# PIC32MZ.net
KiCad netlist of a schematic drawn in Altium Designer
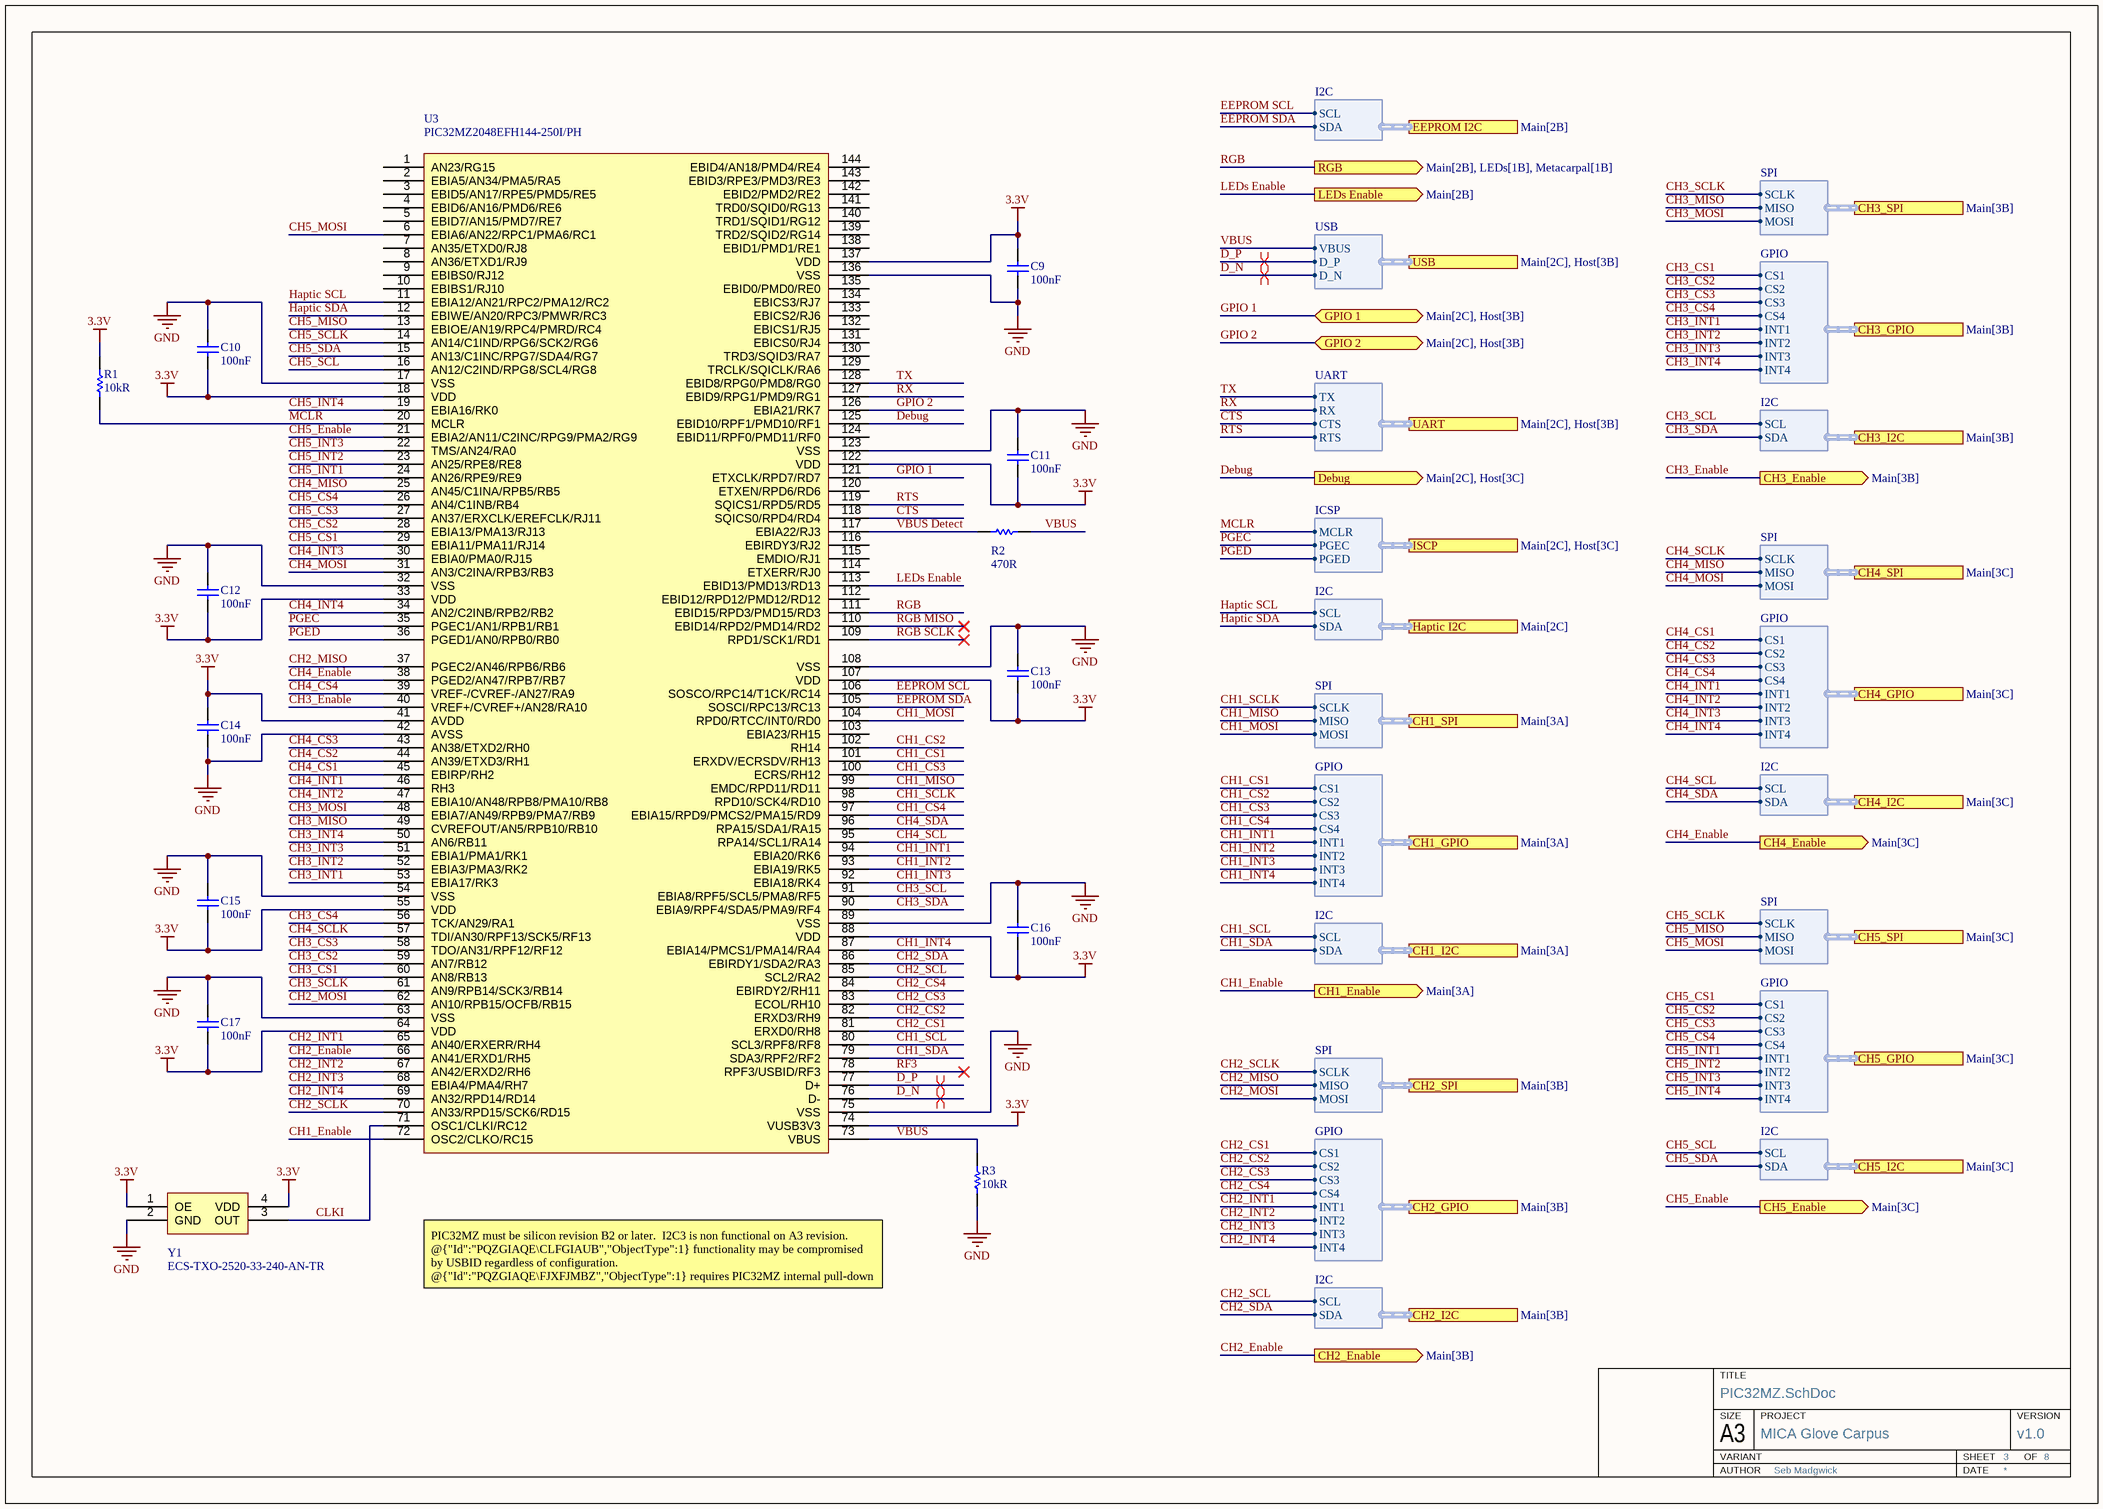
[diagram p0: PIC32MZ.SchDoc]

(export (version "E")
  (design (tool "Eeschema 10.0.6"))
  (components
    (comp (ref "C9") (value "100nF") (footprint "Capacitor 0402") (libsource (lib "x-io") (part "Capacitor")))
    (comp (ref "C10")
      (value "100nF")
      (footprint "Capacitor 0402")
      (libsource (lib "x-io") (part "Capacitor"))
    )
    (comp (ref "C11")
      (value "100nF")
      (footprint "Capacitor 0402")
      (libsource (lib "x-io") (part "Capacitor"))
    )
    (comp (ref "C12")
      (value "100nF")
      (footprint "Capacitor 0402")
      (libsource (lib "x-io") (part "Capacitor"))
    )
    (comp (ref "C13")
      (value "100nF")
      (footprint "Capacitor 0402")
      (libsource (lib "x-io") (part "Capacitor"))
    )
    (comp (ref "C14")
      (value "100nF")
      (footprint "Capacitor 0402")
      (libsource (lib "x-io") (part "Capacitor"))
    )
    (comp (ref "C15")
      (value "100nF")
      (footprint "Capacitor 0402")
      (libsource (lib "x-io") (part "Capacitor"))
    )
    (comp (ref "C16")
      (value "100nF")
      (footprint "Capacitor 0402")
      (libsource (lib "x-io") (part "Capacitor"))
    )
    (comp (ref "C17")
      (value "100nF")
      (footprint "Capacitor 0402")
      (libsource (lib "x-io") (part "Capacitor"))
    )
    (comp (ref "R1") (value "10kR") (footprint "Resistor 0402") (libsource (lib "x-io") (part "Resistor")))
    (comp (ref "R2") (value "470R") (footprint "Resistor 0402") (libsource (lib "x-io") (part "Resistor")))
    (comp (ref "R3") (value "10kR") (footprint "Resistor 0402") (libsource (lib "x-io") (part "Resistor")))
    (comp (ref "U3")
      (value "PIC32MZ2048EFH144-250I/PH")
      (footprint "TQFP-144 0.4mm")
      (libsource (lib "x-io") (part "PIC32MZ2048EFH144-250I/PH"))
    )
    (comp (ref "Y1")
      (value "ECS-TXO-2520-33-240-AN-TR")
      (footprint "ECS 2x2.5mm")
      (libsource (lib "x-io") (part "Oscillator"))
    )
  )
  (nets
    (net (code "7") (name "/CH1_CS1") (class "Default")
      (node (ref "U3") (pin "101") (pinfunction "ERXDV/ECRSDV/RH13_101") (pintype "passive"))
    )
    (net (code "8") (name "/CH1_CS2") (class "Default")
      (node (ref "U3") (pin "102") (pinfunction "RH14_102") (pintype "passive"))
    )
    (net (code "9") (name "/CH1_CS3") (class "Default")
      (node (ref "U3") (pin "100") (pinfunction "ECRS/RH12_100") (pintype "passive"))
    )
    (net (code "10") (name "/CH1_CS4") (class "Default")
      (node (ref "U3") (pin "97") (pinfunction "EBIA15/RPD9/PMCS2/PMA15/RD9_97") (pintype "passive"))
    )
    (net (code "11") (name "/CH1_Enable") (class "Default")
      (node (ref "U3") (pin "72") (pinfunction "OSC2/CLKO/RC15_72") (pintype "passive"))
    )
    (net (code "12") (name "/CH1_INT1") (class "Default")
      (node (ref "U3") (pin "94") (pinfunction "EBIA20/RK6_94") (pintype "passive"))
    )
    (net (code "13") (name "/CH1_INT2") (class "Default")
      (node (ref "U3") (pin "93") (pinfunction "EBIA19/RK5_93") (pintype "passive"))
    )
    (net (code "14") (name "/CH1_INT3") (class "Default")
      (node (ref "U3") (pin "92") (pinfunction "EBIA18/RK4_92") (pintype "passive"))
    )
    (net (code "15") (name "/CH1_INT4") (class "Default")
      (node (ref "U3") (pin "87") (pinfunction "EBIA14/PMCS1/PMA14/RA4_87") (pintype "passive"))
    )
    (net (code "16") (name "/CH1_MISO") (class "Default")
      (node (ref "U3") (pin "99") (pinfunction "EMDC/RPD11/RD11_99") (pintype "passive"))
    )
    (net (code "17") (name "/CH1_MOSI") (class "Default")
      (node (ref "U3") (pin "104") (pinfunction "RPD0/RTCC/INT0/RD0_104") (pintype "passive"))
    )
    (net (code "18") (name "/CH1_SCL") (class "Default")
      (node (ref "U3") (pin "80") (pinfunction "SCL3/RPF8/RF8_80") (pintype "passive"))
    )
    (net (code "19") (name "/CH1_SCLK") (class "Default")
      (node (ref "U3") (pin "98") (pinfunction "RPD10/SCK4/RD10_98") (pintype "passive"))
    )
    (net (code "20") (name "/CH1_SDA") (class "Default")
      (node (ref "U3") (pin "79") (pinfunction "SDA3/RPF2/RF2_79") (pintype "passive"))
    )
    (net (code "21") (name "/CH2_CS1") (class "Default")
      (node (ref "U3") (pin "81") (pinfunction "ERXD0/RH8_81") (pintype "passive"))
    )
    (net (code "22") (name "/CH2_CS2") (class "Default")
      (node (ref "U3") (pin "82") (pinfunction "ERXD3/RH9_82") (pintype "passive"))
    )
    (net (code "23") (name "/CH2_CS3") (class "Default")
      (node (ref "U3") (pin "83") (pinfunction "ECOL/RH10_83") (pintype "passive"))
    )
    (net (code "24") (name "/CH2_CS4") (class "Default")
      (node (ref "U3") (pin "84") (pinfunction "EBIRDY2/RH11_84") (pintype "passive"))
    )
    (net (code "25") (name "/CH2_Enable") (class "Default")
      (node (ref "U3") (pin "66") (pinfunction "AN41/ERXD1/RH5_66") (pintype "passive"))
    )
    (net (code "26") (name "/CH2_INT1") (class "Default")
      (node (ref "U3") (pin "65") (pinfunction "AN40/ERXERR/RH4_65") (pintype "passive"))
    )
    (net (code "27") (name "/CH2_INT2") (class "Default")
      (node (ref "U3") (pin "67") (pinfunction "AN42/ERXD2/RH6_67") (pintype "passive"))
    )
    (net (code "28") (name "/CH2_INT3") (class "Default")
      (node (ref "U3") (pin "68") (pinfunction "EBIA4/PMA4/RH7_68") (pintype "passive"))
    )
    (net (code "29") (name "/CH2_INT4") (class "Default")
      (node (ref "U3") (pin "69") (pinfunction "AN32/RPD14/RD14_69") (pintype "passive"))
    )
    (net (code "30") (name "/CH2_MISO") (class "Default")
      (node (ref "U3") (pin "37") (pinfunction "PGEC2/AN46/RPB6/RB6_37") (pintype "passive"))
    )
    (net (code "31") (name "/CH2_MOSI") (class "Default")
      (node (ref "U3") (pin "62") (pinfunction "AN10/RPB15/OCFB/RB15_62") (pintype "passive"))
    )
    (net (code "32") (name "/CH2_SCL") (class "Default")
      (node (ref "U3") (pin "85") (pinfunction "SCL2/RA2_85") (pintype "passive"))
    )
    (net (code "33") (name "/CH2_SCLK") (class "Default")
      (node (ref "U3") (pin "70") (pinfunction "AN33/RPD15/SCK6/RD15_70") (pintype "passive"))
    )
    (net (code "34") (name "/CH2_SDA") (class "Default")
      (node (ref "U3") (pin "86") (pinfunction "EBIRDY1/SDA2/RA3_86") (pintype "passive"))
    )
    (net (code "35") (name "/CH3_CS1") (class "Default")
      (node (ref "U3") (pin "60") (pinfunction "AN8/RB13_60") (pintype "passive"))
    )
    (net (code "36") (name "/CH3_CS2") (class "Default")
      (node (ref "U3") (pin "59") (pinfunction "AN7/RB12_59") (pintype "passive"))
    )
    (net (code "37") (name "/CH3_CS3") (class "Default")
      (node (ref "U3") (pin "58") (pinfunction "TDO/AN31/RPF12/RF12_58") (pintype "passive"))
    )
    (net (code "38") (name "/CH3_CS4") (class "Default")
      (node (ref "U3") (pin "56") (pinfunction "TCK/AN29/RA1_56") (pintype "passive"))
    )
    (net (code "39") (name "/CH3_Enable") (class "Default")
      (node (ref "U3") (pin "40") (pinfunction "VREF+/CVREF+/AN28/RA10_40") (pintype "passive"))
    )
    (net (code "40") (name "/CH3_INT1") (class "Default")
      (node (ref "U3") (pin "53") (pinfunction "EBIA17/RK3_53") (pintype "passive"))
    )
    (net (code "41") (name "/CH3_INT2") (class "Default")
      (node (ref "U3") (pin "52") (pinfunction "EBIA3/PMA3/RK2_52") (pintype "passive"))
    )
    (net (code "42") (name "/CH3_INT3") (class "Default")
      (node (ref "U3") (pin "51") (pinfunction "EBIA1/PMA1/RK1_51") (pintype "passive"))
    )
    (net (code "43") (name "/CH3_INT4") (class "Default")
      (node (ref "U3") (pin "50") (pinfunction "AN6/RB11_50") (pintype "passive"))
    )
    (net (code "44") (name "/CH3_MISO") (class "Default")
      (node (ref "U3") (pin "49") (pinfunction "CVREFOUT/AN5/RPB10/RB10_49") (pintype "passive"))
    )
    (net (code "45") (name "/CH3_MOSI") (class "Default")
      (node (ref "U3") (pin "48") (pinfunction "EBIA7/AN49/RPB9/PMA7/RB9_48") (pintype "passive"))
    )
    (net (code "46") (name "/CH3_SCL") (class "Default")
      (node (ref "U3") (pin "91") (pinfunction "EBIA8/RPF5/SCL5/PMA8/RF5_91") (pintype "passive"))
    )
    (net (code "47") (name "/CH3_SCLK") (class "Default")
      (node (ref "U3") (pin "61") (pinfunction "AN9/RPB14/SCK3/RB14_61") (pintype "passive"))
    )
    (net (code "48") (name "/CH3_SDA") (class "Default")
      (node (ref "U3") (pin "90") (pinfunction "EBIA9/RPF4/SDA5/PMA9/RF4_90") (pintype "passive"))
    )
    (net (code "49") (name "/CH4_CS1") (class "Default")
      (node (ref "U3") (pin "45") (pinfunction "EBIRP/RH2_45") (pintype "passive"))
    )
    (net (code "50") (name "/CH4_CS2") (class "Default")
      (node (ref "U3") (pin "44") (pinfunction "AN39/ETXD3/RH1_44") (pintype "passive"))
    )
    (net (code "51") (name "/CH4_CS3") (class "Default")
      (node (ref "U3") (pin "43") (pinfunction "AN38/ETXD2/RH0_43") (pintype "passive"))
    )
    (net (code "52") (name "/CH4_CS4") (class "Default")
      (node (ref "U3") (pin "39") (pinfunction "VREF-/CVREF-/AN27/RA9_39") (pintype "passive"))
    )
    (net (code "53") (name "/CH4_Enable") (class "Default")
      (node (ref "U3") (pin "38") (pinfunction "PGED2/AN47/RPB7/RB7_38") (pintype "passive"))
    )
    (net (code "54") (name "/CH4_INT1") (class "Default")
      (node (ref "U3") (pin "46") (pinfunction "RH3_46") (pintype "passive"))
    )
    (net (code "55") (name "/CH4_INT2") (class "Default")
      (node (ref "U3") (pin "47") (pinfunction "EBIA10/AN48/RPB8/PMA10/RB8_47") (pintype "passive"))
    )
    (net (code "56") (name "/CH4_INT3") (class "Default")
      (node (ref "U3") (pin "30") (pinfunction "EBIA0/PMA0/RJ15_30") (pintype "passive"))
    )
    (net (code "57") (name "/CH4_INT4") (class "Default")
      (node (ref "U3") (pin "34") (pinfunction "AN2/C2INB/RPB2/RB2_34") (pintype "passive"))
    )
    (net (code "58") (name "/CH4_MISO") (class "Default")
      (node (ref "U3") (pin "25") (pinfunction "AN45/C1INA/RPB5/RB5_25") (pintype "passive"))
    )
    (net (code "59") (name "/CH4_MOSI") (class "Default")
      (node (ref "U3") (pin "31") (pinfunction "AN3/C2INA/RPB3/RB3_31") (pintype "passive"))
    )
    (net (code "60") (name "/CH4_SCL") (class "Default")
      (node (ref "U3") (pin "95") (pinfunction "RPA14/SCL1/RA14_95") (pintype "passive"))
    )
    (net (code "61") (name "/CH4_SCLK") (class "Default")
      (node (ref "U3") (pin "57") (pinfunction "TDI/AN30/RPF13/SCK5/RF13_57") (pintype "passive"))
    )
    (net (code "62") (name "/CH4_SDA") (class "Default")
      (node (ref "U3") (pin "96") (pinfunction "RPA15/SDA1/RA15_96") (pintype "passive"))
    )
    (net (code "63") (name "/CH5_CS1") (class "Default")
      (node (ref "U3") (pin "29") (pinfunction "EBIA11/PMA11/RJ14_29") (pintype "passive"))
    )
    (net (code "64") (name "/CH5_CS2") (class "Default")
      (node (ref "U3") (pin "28") (pinfunction "EBIA13/PMA13/RJ13_28") (pintype "passive"))
    )
    (net (code "65") (name "/CH5_CS3") (class "Default")
      (node (ref "U3") (pin "27") (pinfunction "AN37/ERXCLK/EREFCLK/RJ11_27") (pintype "passive"))
    )
    (net (code "66") (name "/CH5_CS4") (class "Default")
      (node (ref "U3") (pin "26") (pinfunction "AN4/C1INB/RB4_26") (pintype "passive"))
    )
    (net (code "67") (name "/CH5_Enable") (class "Default")
      (node (ref "U3") (pin "21") (pinfunction "EBIA2/AN11/C2INC/RPG9/PMA2/RG9_21") (pintype "passive"))
    )
    (net (code "68") (name "/CH5_INT1") (class "Default")
      (node (ref "U3") (pin "24") (pinfunction "AN26/RPE9/RE9_24") (pintype "passive"))
    )
    (net (code "69") (name "/CH5_INT2") (class "Default")
      (node (ref "U3") (pin "23") (pinfunction "AN25/RPE8/RE8_23") (pintype "passive"))
    )
    (net (code "70") (name "/CH5_INT3") (class "Default")
      (node (ref "U3") (pin "22") (pinfunction "TMS/AN24/RA0_22") (pintype "passive"))
    )
    (net (code "71") (name "/CH5_INT4") (class "Default")
      (node (ref "U3") (pin "19") (pinfunction "EBIA16/RK0_19") (pintype "passive"))
    )
    (net (code "72") (name "/CH5_MISO") (class "Default")
      (node (ref "U3") (pin "13") (pinfunction "EBIOE/AN19/RPC4/PMRD/RC4_13") (pintype "passive"))
    )
    (net (code "73") (name "/CH5_MOSI") (class "Default")
      (node (ref "U3") (pin "6") (pinfunction "EBIA6/AN22/RPC1/PMA6/RC1_6") (pintype "passive"))
    )
    (net (code "74") (name "/CH5_SCL") (class "Default")
      (node (ref "U3") (pin "16") (pinfunction "AN12/C2IND/RPG8/SCL4/RG8_16") (pintype "passive"))
    )
    (net (code "75") (name "/CH5_SCLK") (class "Default")
      (node (ref "U3") (pin "14") (pinfunction "AN14/C1IND/RPG6/SCK2/RG6_14") (pintype "passive"))
    )
    (net (code "76") (name "/CH5_SDA") (class "Default")
      (node (ref "U3") (pin "15") (pinfunction "AN13/C1INC/RPG7/SDA4/RG7_15") (pintype "passive"))
    )
    (net (code "77") (name "/CLKI") (class "Default")
      (node (ref "U3") (pin "71") (pinfunction "OSC1/CLKI/RC12_71") (pintype "passive"))
      (node (ref "Y1") (pin "3") (pinfunction "OUT_3") (pintype "passive"))
    )
    (net (code "78") (name "/CTS") (class "Default")
      (node (ref "U3") (pin "118") (pinfunction "SQICS0/RPD4/RD4_118") (pintype "passive"))
    )
    (net (code "79") (name "/D_N") (class "Default")
      (node (ref "U3") (pin "76") (pinfunction "D-_76") (pintype "passive"))
    )
    (net (code "80") (name "/D_P") (class "Default")
      (node (ref "U3") (pin "77") (pinfunction "D+_77") (pintype "passive"))
    )
    (net (code "81") (name "/Debug") (class "Default")
      (node (ref "U3") (pin "125") (pinfunction "EBID10/RPF1/PMD10/RF1_125") (pintype "passive"))
    )
    (net (code "82") (name "/EEPROM SCL") (class "Default")
      (node (ref "U3") (pin "106") (pinfunction "SOSCO/RPC14/T1CK/RC14_106") (pintype "passive"))
    )
    (net (code "83") (name "/EEPROM SDA") (class "Default")
      (node (ref "U3") (pin "105") (pinfunction "SOSCI/RPC13/RC13_105") (pintype "passive"))
    )
    (net (code "84") (name "/GPIO 1") (class "Default")
      (node (ref "U3") (pin "121") (pinfunction "ETXCLK/RPD7/RD7_121") (pintype "passive"))
    )
    (net (code "85") (name "/GPIO 2") (class "Default")
      (node (ref "U3") (pin "126") (pinfunction "EBIA21/RK7_126") (pintype "passive"))
    )
    (net (code "86") (name "/Haptic SCL") (class "Default")
      (node (ref "U3") (pin "11") (pinfunction "EBIA12/AN21/RPC2/PMA12/RC2_11") (pintype "passive"))
    )
    (net (code "87") (name "/Haptic SDA") (class "Default")
      (node (ref "U3") (pin "12") (pinfunction "EBIWE/AN20/RPC3/PMWR/RC3_12") (pintype "passive"))
    )
    (net (code "88") (name "/LEDs Enable") (class "Default")
      (node (ref "U3") (pin "113") (pinfunction "EBID13/PMD13/RD13_113") (pintype "passive"))
    )
    (net (code "89") (name "/MCLR") (class "Default")
      (node (ref "R1") (pin "1") (pinfunction "1_1") (pintype "passive"))
      (node (ref "U3") (pin "20") (pinfunction "MCLR_20") (pintype "passive"))
    )
    (net (code "90") (name "/PGEC") (class "Default")
      (node (ref "U3") (pin "35") (pinfunction "PGEC1/AN1/RPB1/RB1_35") (pintype "passive"))
    )
    (net (code "91") (name "/PGED") (class "Default")
      (node (ref "U3") (pin "36") (pinfunction "PGED1/AN0/RPB0/RB0_36") (pintype "passive"))
    )
    (net (code "92") (name "/RF3") (class "Default")
      (node (ref "U3") (pin "78") (pinfunction "RPF3/USBID/RF3_78") (pintype "passive+no_connect"))
    )
    (net (code "93") (name "/RGB") (class "Default")
      (node (ref "U3") (pin "111") (pinfunction "EBID15/RPD3/PMD15/RD3_111") (pintype "passive"))
    )
    (net (code "94") (name "/RGB MISO") (class "Default")
      (node (ref "U3") (pin "110") (pinfunction "EBID14/RPD2/PMD14/RD2_110") (pintype "passive+no_connect"))
    )
    (net (code "95") (name "/RGB SCLK") (class "Default")
      (node (ref "U3") (pin "109") (pinfunction "RPD1/SCK1/RD1_109") (pintype "passive+no_connect"))
    )
    (net (code "96") (name "/RTS") (class "Default")
      (node (ref "U3") (pin "119") (pinfunction "SQICS1/RPD5/RD5_119") (pintype "passive"))
    )
    (net (code "97") (name "/RX") (class "Default")
      (node (ref "U3") (pin "127") (pinfunction "EBID9/RPG1/PMD9/RG1_127") (pintype "passive"))
    )
    (net (code "98") (name "/TX") (class "Default")
      (node (ref "U3") (pin "128") (pinfunction "EBID8/RPG0/PMD8/RG0_128") (pintype "passive"))
    )
    (net (code "99") (name "/VBUS") (class "Default")
      (node (ref "R2") (pin "1") (pinfunction "1_1") (pintype "passive"))
      (node (ref "R3") (pin "2") (pinfunction "2_2") (pintype "passive"))
      (node (ref "U3") (pin "73") (pinfunction "VBUS_73") (pintype "passive"))
    )
    (net (code "100") (name "/VBUS Detect") (class "Default")
      (node (ref "R2") (pin "2") (pinfunction "2_2") (pintype "passive"))
      (node (ref "U3") (pin "117") (pinfunction "EBIA22/RJ3_117") (pintype "passive"))
    )
    (net (code "107") (name "3.3V") (class "Default")
      (node (ref "C10") (pin "1") (pinfunction "1_1") (pintype "passive"))
      (node (ref "C11") (pin "1") (pinfunction "1_1") (pintype "passive"))
      (node (ref "C12") (pin "1") (pinfunction "1_1") (pintype "passive"))
      (node (ref "C13") (pin "1") (pinfunction "1_1") (pintype "passive"))
      (node (ref "C14") (pin "2") (pinfunction "2_2") (pintype "passive"))
      (node (ref "C15") (pin "1") (pinfunction "1_1") (pintype "passive"))
      (node (ref "C16") (pin "1") (pinfunction "1_1") (pintype "passive"))
      (node (ref "C17") (pin "1") (pinfunction "1_1") (pintype "passive"))
      (node (ref "C9") (pin "2") (pinfunction "2_2") (pintype "passive"))
      (node (ref "R1") (pin "2") (pinfunction "2_2") (pintype "passive"))
      (node (ref "U3") (pin "107") (pinfunction "VDD_107") (pintype "passive"))
      (node (ref "U3") (pin "122") (pinfunction "VDD_122") (pintype "passive"))
      (node (ref "U3") (pin "137") (pinfunction "VDD_137") (pintype "passive"))
      (node (ref "U3") (pin "18") (pinfunction "VDD_18") (pintype "passive"))
      (node (ref "U3") (pin "33") (pinfunction "VDD_33") (pintype "passive"))
      (node (ref "U3") (pin "41") (pinfunction "AVDD_41") (pintype "passive"))
      (node (ref "U3") (pin "55") (pinfunction "VDD_55") (pintype "passive"))
      (node (ref "U3") (pin "64") (pinfunction "VDD_64") (pintype "passive"))
      (node (ref "U3") (pin "74") (pinfunction "VUSB3V3_74") (pintype "passive"))
      (node (ref "U3") (pin "88") (pinfunction "VDD_88") (pintype "passive"))
      (node (ref "Y1") (pin "1") (pinfunction "OE_1") (pintype "passive"))
      (node (ref "Y1") (pin "4") (pinfunction "VDD_4") (pintype "passive"))
    )
    (net (code "108") (name "GND") (class "Default")
      (node (ref "C10") (pin "2") (pinfunction "2_2") (pintype "passive"))
      (node (ref "C11") (pin "2") (pinfunction "2_2") (pintype "passive"))
      (node (ref "C12") (pin "2") (pinfunction "2_2") (pintype "passive"))
      (node (ref "C13") (pin "2") (pinfunction "2_2") (pintype "passive"))
      (node (ref "C14") (pin "1") (pinfunction "1_1") (pintype "passive"))
      (node (ref "C15") (pin "2") (pinfunction "2_2") (pintype "passive"))
      (node (ref "C16") (pin "2") (pinfunction "2_2") (pintype "passive"))
      (node (ref "C17") (pin "2") (pinfunction "2_2") (pintype "passive"))
      (node (ref "C9") (pin "1") (pinfunction "1_1") (pintype "passive"))
      (node (ref "R3") (pin "1") (pinfunction "1_1") (pintype "passive"))
      (node (ref "U3") (pin "108") (pinfunction "VSS_108") (pintype "passive"))
      (node (ref "U3") (pin "123") (pinfunction "VSS_123") (pintype "passive"))
      (node (ref "U3") (pin "136") (pinfunction "VSS_136") (pintype "passive"))
      (node (ref "U3") (pin "17") (pinfunction "VSS_17") (pintype "passive"))
      (node (ref "U3") (pin "32") (pinfunction "VSS_32") (pintype "passive"))
      (node (ref "U3") (pin "42") (pinfunction "AVSS_42") (pintype "passive"))
      (node (ref "U3") (pin "54") (pinfunction "VSS_54") (pintype "passive"))
      (node (ref "U3") (pin "63") (pinfunction "VSS_63") (pintype "passive"))
      (node (ref "U3") (pin "75") (pinfunction "VSS_75") (pintype "passive"))
      (node (ref "U3") (pin "89") (pinfunction "VSS_89") (pintype "passive"))
      (node (ref "Y1") (pin "2") (pinfunction "GND_2") (pintype "passive"))
    )
    (net (code "109") (name "unconnected-(U3-AN23{slash}RG15-Pad1)") (class "Default")
      (node (ref "U3") (pin "1") (pinfunction "AN23/RG15_1") (pintype "passive"))
    )
    (net (code "110") (name "unconnected-(U3-AN35{slash}ETXD0{slash}RJ8-Pad7)") (class "Default")
      (node (ref "U3") (pin "7") (pinfunction "AN35/ETXD0/RJ8_7") (pintype "passive"))
    )
    (net (code "111") (name "unconnected-(U3-AN36{slash}ETXD1{slash}RJ9-Pad8)") (class "Default")
      (node (ref "U3") (pin "8") (pinfunction "AN36/ETXD1/RJ9_8") (pintype "passive"))
    )
    (net (code "112") (name "unconnected-(U3-EBIA5{slash}AN34{slash}PMA5{slash}RA5-Pad2)") (class "Default")
      (node (ref "U3") (pin "2") (pinfunction "EBIA5/AN34/PMA5/RA5_2") (pintype "passive"))
    )
    (net (code "113") (name "unconnected-(U3-EBIA23{slash}RH15-Pad103)") (class "Default")
      (node (ref "U3") (pin "103") (pinfunction "EBIA23/RH15_103") (pintype "passive"))
    )
    (net (code "114") (name "unconnected-(U3-EBIBS0{slash}RJ12-Pad9)") (class "Default")
      (node (ref "U3") (pin "9") (pinfunction "EBIBS0/RJ12_9") (pintype "passive"))
    )
    (net (code "115") (name "unconnected-(U3-EBIBS1{slash}RJ10-Pad10)") (class "Default")
      (node (ref "U3") (pin "10") (pinfunction "EBIBS1/RJ10_10") (pintype "passive"))
    )
    (net (code "116") (name "unconnected-(U3-EBICS0{slash}RJ4-Pad131)") (class "Default")
      (node (ref "U3") (pin "131") (pinfunction "EBICS0/RJ4_131") (pintype "passive"))
    )
    (net (code "117") (name "unconnected-(U3-EBICS1{slash}RJ5-Pad132)") (class "Default")
      (node (ref "U3") (pin "132") (pinfunction "EBICS1/RJ5_132") (pintype "passive"))
    )
    (net (code "118") (name "unconnected-(U3-EBICS2{slash}RJ6-Pad133)") (class "Default")
      (node (ref "U3") (pin "133") (pinfunction "EBICS2/RJ6_133") (pintype "passive"))
    )
    (net (code "119") (name "unconnected-(U3-EBICS3{slash}RJ7-Pad134)") (class "Default")
      (node (ref "U3") (pin "134") (pinfunction "EBICS3/RJ7_134") (pintype "passive"))
    )
    (net (code "120") (name "unconnected-(U3-EBID0{slash}PMD0{slash}RE0-Pad135)") (class "Default")
      (node (ref "U3") (pin "135") (pinfunction "EBID0/PMD0/RE0_135") (pintype "passive"))
    )
    (net (code "121") (name "unconnected-(U3-EBID1{slash}PMD1{slash}RE1-Pad138)") (class "Default")
      (node (ref "U3") (pin "138") (pinfunction "EBID1/PMD1/RE1_138") (pintype "passive"))
    )
    (net (code "122") (name "unconnected-(U3-EBID2{slash}PMD2{slash}RE2-Pad142)") (class "Default")
      (node (ref "U3") (pin "142") (pinfunction "EBID2/PMD2/RE2_142") (pintype "passive"))
    )
    (net (code "123") (name "unconnected-(U3-EBID3{slash}RPE3{slash}PMD3{slash}RE3-Pad143)") (class "Default")
      (node (ref "U3") (pin "143") (pinfunction "EBID3/RPE3/PMD3/RE3_143") (pintype "passive"))
    )
    (net (code "124") (name "unconnected-(U3-EBID4{slash}AN18{slash}PMD4{slash}RE4-Pad144)") (class "Default")
      (node (ref "U3") (pin "144") (pinfunction "EBID4/AN18/PMD4/RE4_144") (pintype "passive"))
    )
    (net (code "125") (name "unconnected-(U3-EBID5{slash}AN17{slash}RPE5{slash}PMD5{slash}RE5-Pad3)") (class "Default")
      (node (ref "U3") (pin "3") (pinfunction "EBID5/AN17/RPE5/PMD5/RE5_3") (pintype "passive"))
    )
    (net (code "126") (name "unconnected-(U3-EBID6{slash}AN16{slash}PMD6{slash}RE6-Pad4)") (class "Default")
      (node (ref "U3") (pin "4") (pinfunction "EBID6/AN16/PMD6/RE6_4") (pintype "passive"))
    )
    (net (code "127") (name "unconnected-(U3-EBID7{slash}AN15{slash}PMD7{slash}RE7-Pad5)") (class "Default")
      (node (ref "U3") (pin "5") (pinfunction "EBID7/AN15/PMD7/RE7_5") (pintype "passive"))
    )
    (net (code "128") (name "unconnected-(U3-EBID11{slash}RPF0{slash}PMD11{slash}RF0-Pad124)") (class "Default")
      (node (ref "U3") (pin "124") (pinfunction "EBID11/RPF0/PMD11/RF0_124") (pintype "passive"))
    )
    (net (code "129") (name "unconnected-(U3-EBID12{slash}RPD12{slash}PMD12{slash}RD12-Pad112)") (class "Default")
      (node (ref "U3") (pin "112") (pinfunction "EBID12/RPD12/PMD12/RD12_112") (pintype "passive"))
    )
    (net (code "130") (name "unconnected-(U3-EBIRDY3{slash}RJ2-Pad116)") (class "Default")
      (node (ref "U3") (pin "116") (pinfunction "EBIRDY3/RJ2_116") (pintype "passive"))
    )
    (net (code "131") (name "unconnected-(U3-EMDIO{slash}RJ1-Pad115)") (class "Default")
      (node (ref "U3") (pin "115") (pinfunction "EMDIO/RJ1_115") (pintype "passive"))
    )
    (net (code "132") (name "unconnected-(U3-ETXEN{slash}RPD6{slash}RD6-Pad120)") (class "Default")
      (node (ref "U3") (pin "120") (pinfunction "ETXEN/RPD6/RD6_120") (pintype "passive"))
    )
    (net (code "133") (name "unconnected-(U3-ETXERR{slash}RJ0-Pad114)") (class "Default")
      (node (ref "U3") (pin "114") (pinfunction "ETXERR/RJ0_114") (pintype "passive"))
    )
    (net (code "134") (name "unconnected-(U3-TRCLK{slash}SQICLK{slash}RA6-Pad129)") (class "Default")
      (node (ref "U3") (pin "129") (pinfunction "TRCLK/SQICLK/RA6_129") (pintype "passive"))
    )
    (net (code "135") (name "unconnected-(U3-TRD0{slash}SQID0{slash}RG13-Pad141)") (class "Default")
      (node (ref "U3") (pin "141") (pinfunction "TRD0/SQID0/RG13_141") (pintype "passive"))
    )
    (net (code "136") (name "unconnected-(U3-TRD1{slash}SQID1{slash}RG12-Pad140)") (class "Default")
      (node (ref "U3") (pin "140") (pinfunction "TRD1/SQID1/RG12_140") (pintype "passive"))
    )
    (net (code "137") (name "unconnected-(U3-TRD2{slash}SQID2{slash}RG14-Pad139)") (class "Default")
      (node (ref "U3") (pin "139") (pinfunction "TRD2/SQID2/RG14_139") (pintype "passive"))
    )
    (net (code "138") (name "unconnected-(U3-TRD3{slash}SQID3{slash}RA7-Pad130)") (class "Default")
      (node (ref "U3") (pin "130") (pinfunction "TRD3/SQID3/RA7_130") (pintype "passive"))
    )
  )
)
